# LED_Controller_Power.net
KiCad netlist of a schematic drawn in Altium Designer
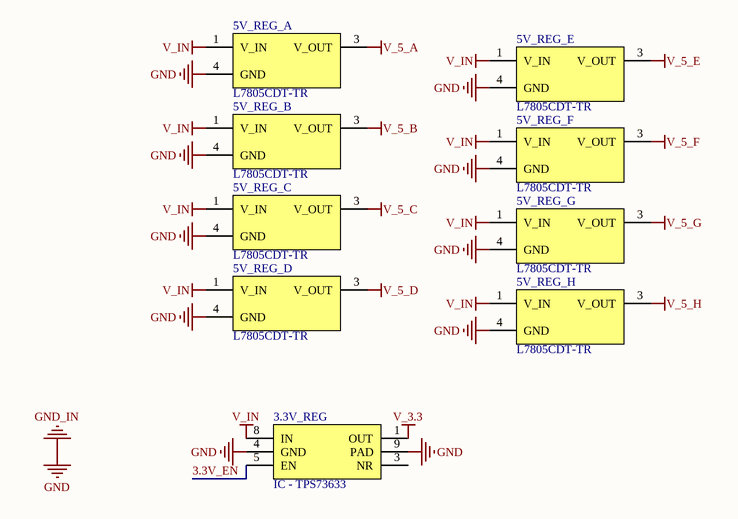
[diagram p0: LED_Controller_Power.SchDoc]

(export (version "E")
  (design (tool "Eeschema 10.0.6"))
  (components
    (comp (ref "3.3V_REG")
      (value "IC - TPS73633")
      (footprint "TI - DRB / QFN65P300X300X100-8L")
      (description "IC LDO REG 400MA NO CAP 8-SON")
      (fields
        (field (name "MANUFACTURER") "Texas Instruments")
        (field (name "MANUFACTURER PART NUMBER") "TPS73633DRBR")
      )
      (libsource (lib "My Schematic Library") (part "IC - TPS73633"))
    )
    (comp (ref "5V_REG_A")
      (value "L7805CDT-TR")
      (footprint "TO228P973X240-3N")
      (description "IC REG POS 1.5A 5V PREC DPAK")
      (fields (field (name "MANUFACTURER") "STMicroelectronics"))
      (libsource (lib "My Schematic Library") (part "IC - L7805CDT-TR"))
    )
    (comp (ref "5V_REG_B")
      (value "L7805CDT-TR")
      (footprint "TO228P973X240-3N")
      (description "IC REG POS 1.5A 5V PREC DPAK")
      (fields (field (name "MANUFACTURER") "STMicroelectronics"))
      (libsource (lib "My Schematic Library") (part "IC - L7805CDT-TR"))
    )
    (comp (ref "5V_REG_C")
      (value "L7805CDT-TR")
      (footprint "TO228P973X240-3N")
      (description "IC REG POS 1.5A 5V PREC DPAK")
      (fields (field (name "MANUFACTURER") "STMicroelectronics"))
      (libsource (lib "My Schematic Library") (part "IC - L7805CDT-TR"))
    )
    (comp (ref "5V_REG_D")
      (value "L7805CDT-TR")
      (footprint "TO228P973X240-3N")
      (description "IC REG POS 1.5A 5V PREC DPAK")
      (fields (field (name "MANUFACTURER") "STMicroelectronics"))
      (libsource (lib "My Schematic Library") (part "IC - L7805CDT-TR"))
    )
    (comp (ref "5V_REG_E")
      (value "L7805CDT-TR")
      (footprint "TO228P973X240-3N")
      (description "IC REG POS 1.5A 5V PREC DPAK")
      (fields (field (name "MANUFACTURER") "STMicroelectronics"))
      (libsource (lib "My Schematic Library") (part "IC - L7805CDT-TR"))
    )
    (comp (ref "5V_REG_F")
      (value "L7805CDT-TR")
      (footprint "TO228P973X240-3N")
      (description "IC REG POS 1.5A 5V PREC DPAK")
      (fields (field (name "MANUFACTURER") "STMicroelectronics"))
      (libsource (lib "My Schematic Library") (part "IC - L7805CDT-TR"))
    )
    (comp (ref "5V_REG_G")
      (value "L7805CDT-TR")
      (footprint "TO228P973X240-3N")
      (description "IC REG POS 1.5A 5V PREC DPAK")
      (fields (field (name "MANUFACTURER") "STMicroelectronics"))
      (libsource (lib "My Schematic Library") (part "IC - L7805CDT-TR"))
    )
    (comp (ref "5V_REG_H")
      (value "L7805CDT-TR")
      (footprint "TO228P973X240-3N")
      (description "IC REG POS 1.5A 5V PREC DPAK")
      (fields (field (name "MANUFACTURER") "STMicroelectronics"))
      (libsource (lib "My Schematic Library") (part "IC - L7805CDT-TR"))
    )
  )
  (nets
    (net (code "1") (name "/3.3V_EN") (class "Default")
      (node (ref "3.3V_REG") (pin "5") (pinfunction "EN_5") (pintype "passive"))
    )
    (net (code "2") (name "GND") (class "Default")
      (node (ref "3.3V_REG") (pin "4") (pinfunction "GND_4") (pintype "passive"))
      (node (ref "3.3V_REG") (pin "9") (pinfunction "PAD_9") (pintype "passive"))
      (node (ref "5V_REG_A") (pin "4") (pinfunction "GND_4") (pintype "passive"))
      (node (ref "5V_REG_B") (pin "4") (pinfunction "GND_4") (pintype "passive"))
      (node (ref "5V_REG_C") (pin "4") (pinfunction "GND_4") (pintype "passive"))
      (node (ref "5V_REG_D") (pin "4") (pinfunction "GND_4") (pintype "passive"))
      (node (ref "5V_REG_E") (pin "4") (pinfunction "GND_4") (pintype "passive"))
      (node (ref "5V_REG_F") (pin "4") (pinfunction "GND_4") (pintype "passive"))
      (node (ref "5V_REG_G") (pin "4") (pinfunction "GND_4") (pintype "passive"))
      (node (ref "5V_REG_H") (pin "4") (pinfunction "GND_4") (pintype "passive"))
    )
    (net (code "3") (name "V_3.3") (class "Default")
      (node (ref "3.3V_REG") (pin "1") (pinfunction "OUT_1") (pintype "passive"))
    )
    (net (code "4") (name "V_5_A") (class "Default")
      (node (ref "5V_REG_A") (pin "3") (pinfunction "V_OUT_3") (pintype "passive"))
    )
    (net (code "5") (name "V_5_B") (class "Default")
      (node (ref "5V_REG_B") (pin "3") (pinfunction "V_OUT_3") (pintype "passive"))
    )
    (net (code "6") (name "V_5_C") (class "Default")
      (node (ref "5V_REG_C") (pin "3") (pinfunction "V_OUT_3") (pintype "passive"))
    )
    (net (code "7") (name "V_5_D") (class "Default")
      (node (ref "5V_REG_D") (pin "3") (pinfunction "V_OUT_3") (pintype "passive"))
    )
    (net (code "8") (name "V_5_E") (class "Default")
      (node (ref "5V_REG_E") (pin "3") (pinfunction "V_OUT_3") (pintype "passive"))
    )
    (net (code "9") (name "V_5_F") (class "Default")
      (node (ref "5V_REG_F") (pin "3") (pinfunction "V_OUT_3") (pintype "passive"))
    )
    (net (code "10") (name "V_5_G") (class "Default")
      (node (ref "5V_REG_G") (pin "3") (pinfunction "V_OUT_3") (pintype "passive"))
    )
    (net (code "11") (name "V_5_H") (class "Default")
      (node (ref "5V_REG_H") (pin "3") (pinfunction "V_OUT_3") (pintype "passive"))
    )
    (net (code "12") (name "V_IN") (class "Default")
      (node (ref "3.3V_REG") (pin "8") (pinfunction "IN_8") (pintype "passive"))
      (node (ref "5V_REG_A") (pin "1") (pinfunction "V_IN_1") (pintype "passive"))
      (node (ref "5V_REG_B") (pin "1") (pinfunction "V_IN_1") (pintype "passive"))
      (node (ref "5V_REG_C") (pin "1") (pinfunction "V_IN_1") (pintype "passive"))
      (node (ref "5V_REG_D") (pin "1") (pinfunction "V_IN_1") (pintype "passive"))
      (node (ref "5V_REG_E") (pin "1") (pinfunction "V_IN_1") (pintype "passive"))
      (node (ref "5V_REG_F") (pin "1") (pinfunction "V_IN_1") (pintype "passive"))
      (node (ref "5V_REG_G") (pin "1") (pinfunction "V_IN_1") (pintype "passive"))
      (node (ref "5V_REG_H") (pin "1") (pinfunction "V_IN_1") (pintype "passive"))
    )
    (net (code "13") (name "unconnected-(3.3V_REG-NR-Pad3)") (class "Default")
      (node (ref "3.3V_REG") (pin "3") (pinfunction "NR_3") (pintype "passive"))
    )
  )
)
